# 05_FPGA_Interface.net
KiCad netlist of a schematic drawn in Altium Designer
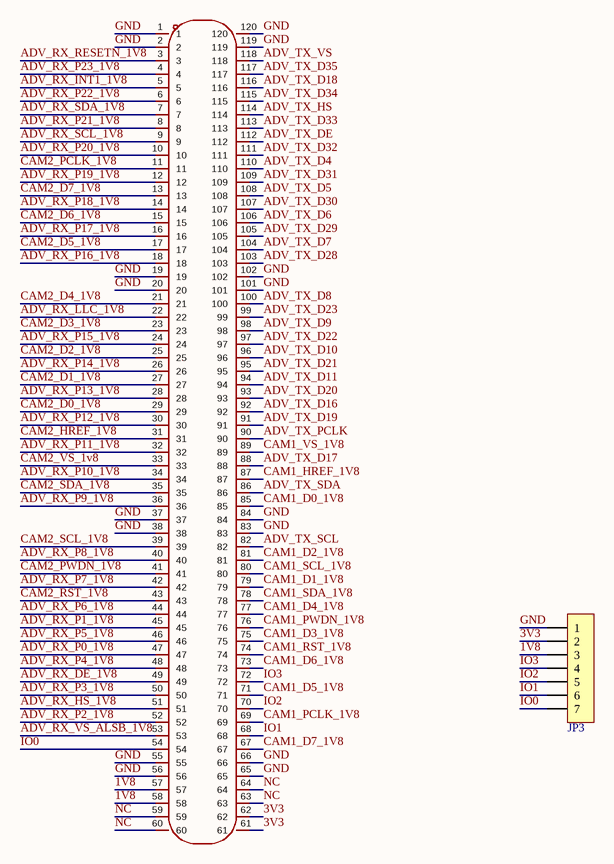
[diagram p0: 05_FPGA_Interface.SchDoc]

(export (version "E")
  (design (tool "Eeschema 10.0.6"))
  (components
    (comp (ref "CN1")
      (value "xdb612-120p-cor")
      (footprint "CONN-SMD_120P-P0.80_THD0812F-120BV-GF")
      (description "PIN总数:120P;间距:0.8mm;安装方式:立贴;排数:2;额定电流:500mA;工作温度:-45℃~+80℃;")
      (fields (field (name "MANUFACTURER") "LX(连欣科技)") (field (name "MANUFACTURERPART") "XDB612-120P-COR"))
      (libsource (lib "0.0self_build") (part "xdb612-120p-cor"))
    )
    (comp (ref "JP3")
      (value "HDR-1X7")
      (footprint "HDR2.54-LI-7P")
      (description "7P接插件")
      (fields (field (name "版权归属") "封装库来自淘宝 ID：黄晶宝石"))
      (libsource (lib "5.3 - 接插件-脚距2.54 (100mil) ") (part "Header 7"))
    )
  )
  (nets
    (net (code "1") (name "/1V8") (class "Default")
      (node (ref "CN1") (pin "57") (pinfunction "57_57") (pintype "passive"))
      (node (ref "CN1") (pin "58") (pinfunction "58_58") (pintype "passive"))
      (node (ref "JP3") (pin "3") (pinfunction "3_3") (pintype "passive"))
    )
    (net (code "2") (name "/3V3") (class "Default")
      (node (ref "CN1") (pin "61") (pinfunction "61_61") (pintype "passive"))
      (node (ref "CN1") (pin "62") (pinfunction "62_62") (pintype "passive"))
      (node (ref "JP3") (pin "2") (pinfunction "2_2") (pintype "passive"))
    )
    (net (code "3") (name "/ADV_RX_DE_1V8") (class "Default")
      (node (ref "CN1") (pin "49") (pinfunction "49_49") (pintype "passive"))
    )
    (net (code "4") (name "/ADV_RX_HS_1V8") (class "Default")
      (node (ref "CN1") (pin "51") (pinfunction "51_51") (pintype "passive"))
    )
    (net (code "5") (name "/ADV_RX_INT1_1V8") (class "Default")
      (node (ref "CN1") (pin "5") (pinfunction "5_5") (pintype "passive"))
    )
    (net (code "6") (name "/ADV_RX_LLC_1V8") (class "Default")
      (node (ref "CN1") (pin "22") (pinfunction "22_22") (pintype "passive"))
    )
    (net (code "7") (name "/ADV_RX_P0_1V8") (class "Default")
      (node (ref "CN1") (pin "47") (pinfunction "47_47") (pintype "passive"))
    )
    (net (code "8") (name "/ADV_RX_P1_1V8") (class "Default")
      (node (ref "CN1") (pin "45") (pinfunction "45_45") (pintype "passive"))
    )
    (net (code "9") (name "/ADV_RX_P2_1V8") (class "Default")
      (node (ref "CN1") (pin "52") (pinfunction "52_52") (pintype "passive"))
    )
    (net (code "10") (name "/ADV_RX_P3_1V8") (class "Default")
      (node (ref "CN1") (pin "50") (pinfunction "50_50") (pintype "passive"))
    )
    (net (code "11") (name "/ADV_RX_P4_1V8") (class "Default")
      (node (ref "CN1") (pin "48") (pinfunction "48_48") (pintype "passive"))
    )
    (net (code "12") (name "/ADV_RX_P5_1V8") (class "Default")
      (node (ref "CN1") (pin "46") (pinfunction "46_46") (pintype "passive"))
    )
    (net (code "13") (name "/ADV_RX_P6_1V8") (class "Default")
      (node (ref "CN1") (pin "44") (pinfunction "44_44") (pintype "passive"))
    )
    (net (code "14") (name "/ADV_RX_P7_1V8") (class "Default")
      (node (ref "CN1") (pin "42") (pinfunction "42_42") (pintype "passive"))
    )
    (net (code "15") (name "/ADV_RX_P8_1V8") (class "Default")
      (node (ref "CN1") (pin "40") (pinfunction "40_40") (pintype "passive"))
    )
    (net (code "16") (name "/ADV_RX_P9_1V8") (class "Default")
      (node (ref "CN1") (pin "36") (pinfunction "36_36") (pintype "passive"))
    )
    (net (code "17") (name "/ADV_RX_P10_1V8") (class "Default")
      (node (ref "CN1") (pin "34") (pinfunction "34_34") (pintype "passive"))
    )
    (net (code "18") (name "/ADV_RX_P11_1V8") (class "Default")
      (node (ref "CN1") (pin "32") (pinfunction "32_32") (pintype "passive"))
    )
    (net (code "19") (name "/ADV_RX_P12_1V8") (class "Default")
      (node (ref "CN1") (pin "30") (pinfunction "30_30") (pintype "passive"))
    )
    (net (code "20") (name "/ADV_RX_P13_1V8") (class "Default")
      (node (ref "CN1") (pin "28") (pinfunction "28_28") (pintype "passive"))
    )
    (net (code "21") (name "/ADV_RX_P14_1V8") (class "Default")
      (node (ref "CN1") (pin "26") (pinfunction "26_26") (pintype "passive"))
    )
    (net (code "22") (name "/ADV_RX_P15_1V8") (class "Default")
      (node (ref "CN1") (pin "24") (pinfunction "24_24") (pintype "passive"))
    )
    (net (code "23") (name "/ADV_RX_P16_1V8") (class "Default")
      (node (ref "CN1") (pin "18") (pinfunction "18_18") (pintype "passive"))
    )
    (net (code "24") (name "/ADV_RX_P17_1V8") (class "Default")
      (node (ref "CN1") (pin "16") (pinfunction "16_16") (pintype "passive"))
    )
    (net (code "25") (name "/ADV_RX_P18_1V8") (class "Default")
      (node (ref "CN1") (pin "14") (pinfunction "14_14") (pintype "passive"))
    )
    (net (code "26") (name "/ADV_RX_P19_1V8") (class "Default")
      (node (ref "CN1") (pin "12") (pinfunction "12_12") (pintype "passive"))
    )
    (net (code "27") (name "/ADV_RX_P20_1V8") (class "Default")
      (node (ref "CN1") (pin "10") (pinfunction "10_10") (pintype "passive"))
    )
    (net (code "28") (name "/ADV_RX_P21_1V8") (class "Default")
      (node (ref "CN1") (pin "8") (pinfunction "8_8") (pintype "passive"))
    )
    (net (code "29") (name "/ADV_RX_P22_1V8") (class "Default")
      (node (ref "CN1") (pin "6") (pinfunction "6_6") (pintype "passive"))
    )
    (net (code "30") (name "/ADV_RX_P23_1V8") (class "Default")
      (node (ref "CN1") (pin "4") (pinfunction "4_4") (pintype "passive"))
    )
    (net (code "31") (name "/ADV_RX_RESETN_1V8") (class "Default")
      (node (ref "CN1") (pin "3") (pinfunction "3_3") (pintype "passive"))
    )
    (net (code "32") (name "/ADV_RX_SCL_1V8") (class "Default")
      (node (ref "CN1") (pin "9") (pinfunction "9_9") (pintype "passive"))
    )
    (net (code "33") (name "/ADV_RX_SDA_1V8") (class "Default")
      (node (ref "CN1") (pin "7") (pinfunction "7_7") (pintype "passive"))
    )
    (net (code "34") (name "/ADV_RX_VS_ALSB_1V8") (class "Default")
      (node (ref "CN1") (pin "53") (pinfunction "53_53") (pintype "passive"))
    )
    (net (code "35") (name "/ADV_TX_D4") (class "Default")
      (node (ref "CN1") (pin "110") (pinfunction "110_110") (pintype "passive"))
    )
    (net (code "36") (name "/ADV_TX_D5") (class "Default")
      (node (ref "CN1") (pin "108") (pinfunction "108_108") (pintype "passive"))
    )
    (net (code "37") (name "/ADV_TX_D6") (class "Default")
      (node (ref "CN1") (pin "106") (pinfunction "106_106") (pintype "passive"))
    )
    (net (code "38") (name "/ADV_TX_D7") (class "Default")
      (node (ref "CN1") (pin "104") (pinfunction "104_104") (pintype "passive"))
    )
    (net (code "39") (name "/ADV_TX_D8") (class "Default")
      (node (ref "CN1") (pin "100") (pinfunction "100_100") (pintype "passive"))
    )
    (net (code "40") (name "/ADV_TX_D9") (class "Default")
      (node (ref "CN1") (pin "98") (pinfunction "98_98") (pintype "passive"))
    )
    (net (code "41") (name "/ADV_TX_D10") (class "Default")
      (node (ref "CN1") (pin "96") (pinfunction "96_96") (pintype "passive"))
    )
    (net (code "42") (name "/ADV_TX_D11") (class "Default")
      (node (ref "CN1") (pin "94") (pinfunction "94_94") (pintype "passive"))
    )
    (net (code "43") (name "/ADV_TX_D16") (class "Default")
      (node (ref "CN1") (pin "92") (pinfunction "92_92") (pintype "passive"))
    )
    (net (code "44") (name "/ADV_TX_D17") (class "Default")
      (node (ref "CN1") (pin "88") (pinfunction "88_88") (pintype "passive"))
    )
    (net (code "45") (name "/ADV_TX_D18") (class "Default")
      (node (ref "CN1") (pin "116") (pinfunction "116_116") (pintype "passive"))
    )
    (net (code "46") (name "/ADV_TX_D19") (class "Default")
      (node (ref "CN1") (pin "91") (pinfunction "91_91") (pintype "passive"))
    )
    (net (code "47") (name "/ADV_TX_D20") (class "Default")
      (node (ref "CN1") (pin "93") (pinfunction "93_93") (pintype "passive"))
    )
    (net (code "48") (name "/ADV_TX_D21") (class "Default")
      (node (ref "CN1") (pin "95") (pinfunction "95_95") (pintype "passive"))
    )
    (net (code "49") (name "/ADV_TX_D22") (class "Default")
      (node (ref "CN1") (pin "97") (pinfunction "97_97") (pintype "passive"))
    )
    (net (code "50") (name "/ADV_TX_D23") (class "Default")
      (node (ref "CN1") (pin "99") (pinfunction "99_99") (pintype "passive"))
    )
    (net (code "51") (name "/ADV_TX_D28") (class "Default")
      (node (ref "CN1") (pin "103") (pinfunction "103_103") (pintype "passive"))
    )
    (net (code "52") (name "/ADV_TX_D29") (class "Default")
      (node (ref "CN1") (pin "105") (pinfunction "105_105") (pintype "passive"))
    )
    (net (code "53") (name "/ADV_TX_D30") (class "Default")
      (node (ref "CN1") (pin "107") (pinfunction "107_107") (pintype "passive"))
    )
    (net (code "54") (name "/ADV_TX_D31") (class "Default")
      (node (ref "CN1") (pin "109") (pinfunction "109_109") (pintype "passive"))
    )
    (net (code "55") (name "/ADV_TX_D32") (class "Default")
      (node (ref "CN1") (pin "111") (pinfunction "111_111") (pintype "passive"))
    )
    (net (code "56") (name "/ADV_TX_D33") (class "Default")
      (node (ref "CN1") (pin "113") (pinfunction "113_113") (pintype "passive"))
    )
    (net (code "57") (name "/ADV_TX_D34") (class "Default")
      (node (ref "CN1") (pin "115") (pinfunction "115_115") (pintype "passive"))
    )
    (net (code "58") (name "/ADV_TX_D35") (class "Default")
      (node (ref "CN1") (pin "117") (pinfunction "117_117") (pintype "passive"))
    )
    (net (code "59") (name "/ADV_TX_DE") (class "Default")
      (node (ref "CN1") (pin "112") (pinfunction "112_112") (pintype "passive"))
    )
    (net (code "60") (name "/ADV_TX_HS") (class "Default")
      (node (ref "CN1") (pin "114") (pinfunction "114_114") (pintype "passive"))
    )
    (net (code "61") (name "/ADV_TX_PCLK") (class "Default")
      (node (ref "CN1") (pin "90") (pinfunction "90_90") (pintype "passive"))
    )
    (net (code "62") (name "/ADV_TX_SCL") (class "Default")
      (node (ref "CN1") (pin "82") (pinfunction "82_82") (pintype "passive"))
    )
    (net (code "63") (name "/ADV_TX_SDA") (class "Default")
      (node (ref "CN1") (pin "86") (pinfunction "86_86") (pintype "passive"))
    )
    (net (code "64") (name "/ADV_TX_VS") (class "Default")
      (node (ref "CN1") (pin "118") (pinfunction "118_118") (pintype "passive"))
    )
    (net (code "65") (name "/CAM1_D0_1V8") (class "Default")
      (node (ref "CN1") (pin "85") (pinfunction "85_85") (pintype "passive"))
    )
    (net (code "66") (name "/CAM1_D1_1V8") (class "Default")
      (node (ref "CN1") (pin "79") (pinfunction "79_79") (pintype "passive"))
    )
    (net (code "67") (name "/CAM1_D2_1V8") (class "Default")
      (node (ref "CN1") (pin "81") (pinfunction "81_81") (pintype "passive"))
    )
    (net (code "68") (name "/CAM1_D3_1V8") (class "Default")
      (node (ref "CN1") (pin "75") (pinfunction "75_75") (pintype "passive"))
    )
    (net (code "69") (name "/CAM1_D4_1V8") (class "Default")
      (node (ref "CN1") (pin "77") (pinfunction "77_77") (pintype "passive"))
    )
    (net (code "70") (name "/CAM1_D5_1V8") (class "Default")
      (node (ref "CN1") (pin "71") (pinfunction "71_71") (pintype "passive"))
    )
    (net (code "71") (name "/CAM1_D6_1V8") (class "Default")
      (node (ref "CN1") (pin "73") (pinfunction "73_73") (pintype "passive"))
    )
    (net (code "72") (name "/CAM1_D7_1V8") (class "Default")
      (node (ref "CN1") (pin "67") (pinfunction "67_67") (pintype "passive"))
    )
    (net (code "73") (name "/CAM1_HREF_1V8") (class "Default")
      (node (ref "CN1") (pin "87") (pinfunction "87_87") (pintype "passive"))
    )
    (net (code "74") (name "/CAM1_PCLK_1V8") (class "Default")
      (node (ref "CN1") (pin "69") (pinfunction "69_69") (pintype "passive"))
    )
    (net (code "75") (name "/CAM1_PWDN_1V8") (class "Default")
      (node (ref "CN1") (pin "76") (pinfunction "76_76") (pintype "passive"))
    )
    (net (code "76") (name "/CAM1_RST_1V8") (class "Default")
      (node (ref "CN1") (pin "74") (pinfunction "74_74") (pintype "passive"))
    )
    (net (code "77") (name "/CAM1_SCL_1V8") (class "Default")
      (node (ref "CN1") (pin "80") (pinfunction "80_80") (pintype "passive"))
    )
    (net (code "78") (name "/CAM1_SDA_1V8") (class "Default")
      (node (ref "CN1") (pin "78") (pinfunction "78_78") (pintype "passive"))
    )
    (net (code "79") (name "/CAM1_VS_1V8") (class "Default")
      (node (ref "CN1") (pin "89") (pinfunction "89_89") (pintype "passive"))
    )
    (net (code "80") (name "/CAM2_D0_1V8") (class "Default")
      (node (ref "CN1") (pin "29") (pinfunction "29_29") (pintype "passive"))
    )
    (net (code "81") (name "/CAM2_D1_1V8") (class "Default")
      (node (ref "CN1") (pin "27") (pinfunction "27_27") (pintype "passive"))
    )
    (net (code "82") (name "/CAM2_D2_1V8") (class "Default")
      (node (ref "CN1") (pin "25") (pinfunction "25_25") (pintype "passive"))
    )
    (net (code "83") (name "/CAM2_D3_1V8") (class "Default")
      (node (ref "CN1") (pin "23") (pinfunction "23_23") (pintype "passive"))
    )
    (net (code "84") (name "/CAM2_D4_1V8") (class "Default")
      (node (ref "CN1") (pin "21") (pinfunction "21_21") (pintype "passive"))
    )
    (net (code "85") (name "/CAM2_D5_1V8") (class "Default")
      (node (ref "CN1") (pin "17") (pinfunction "17_17") (pintype "passive"))
    )
    (net (code "86") (name "/CAM2_D6_1V8") (class "Default")
      (node (ref "CN1") (pin "15") (pinfunction "15_15") (pintype "passive"))
    )
    (net (code "87") (name "/CAM2_D7_1V8") (class "Default")
      (node (ref "CN1") (pin "13") (pinfunction "13_13") (pintype "passive"))
    )
    (net (code "88") (name "/CAM2_HREF_1V8") (class "Default")
      (node (ref "CN1") (pin "31") (pinfunction "31_31") (pintype "passive"))
    )
    (net (code "89") (name "/CAM2_PCLK_1V8") (class "Default")
      (node (ref "CN1") (pin "11") (pinfunction "11_11") (pintype "passive"))
    )
    (net (code "90") (name "/CAM2_PWDN_1V8") (class "Default")
      (node (ref "CN1") (pin "41") (pinfunction "41_41") (pintype "passive"))
    )
    (net (code "91") (name "/CAM2_RST_1V8") (class "Default")
      (node (ref "CN1") (pin "43") (pinfunction "43_43") (pintype "passive"))
    )
    (net (code "92") (name "/CAM2_SCL_1V8") (class "Default")
      (node (ref "CN1") (pin "39") (pinfunction "39_39") (pintype "passive"))
    )
    (net (code "93") (name "/CAM2_SDA_1V8") (class "Default")
      (node (ref "CN1") (pin "35") (pinfunction "35_35") (pintype "passive"))
    )
    (net (code "94") (name "/CAM2_VS_1v8") (class "Default")
      (node (ref "CN1") (pin "33") (pinfunction "33_33") (pintype "passive"))
    )
    (net (code "95") (name "/GND") (class "Default")
      (node (ref "CN1") (pin "1") (pinfunction "1_1") (pintype "passive"))
      (node (ref "CN1") (pin "101") (pinfunction "101_101") (pintype "passive"))
      (node (ref "CN1") (pin "102") (pinfunction "102_102") (pintype "passive"))
      (node (ref "CN1") (pin "119") (pinfunction "119_119") (pintype "passive"))
      (node (ref "CN1") (pin "120") (pinfunction "120_120") (pintype "passive"))
      (node (ref "CN1") (pin "19") (pinfunction "19_19") (pintype "passive"))
      (node (ref "CN1") (pin "2") (pinfunction "2_2") (pintype "passive"))
      (node (ref "CN1") (pin "20") (pinfunction "20_20") (pintype "passive"))
      (node (ref "CN1") (pin "37") (pinfunction "37_37") (pintype "passive"))
      (node (ref "CN1") (pin "38") (pinfunction "38_38") (pintype "passive"))
      (node (ref "CN1") (pin "55") (pinfunction "55_55") (pintype "passive"))
      (node (ref "CN1") (pin "56") (pinfunction "56_56") (pintype "passive"))
      (node (ref "CN1") (pin "65") (pinfunction "65_65") (pintype "passive"))
      (node (ref "CN1") (pin "66") (pinfunction "66_66") (pintype "passive"))
      (node (ref "CN1") (pin "83") (pinfunction "83_83") (pintype "passive"))
      (node (ref "CN1") (pin "84") (pinfunction "84_84") (pintype "passive"))
      (node (ref "JP3") (pin "1") (pinfunction "1_1") (pintype "passive"))
    )
    (net (code "96") (name "/IO0") (class "Default")
      (node (ref "CN1") (pin "54") (pinfunction "54_54") (pintype "passive"))
      (node (ref "JP3") (pin "7") (pinfunction "7_7") (pintype "passive"))
    )
    (net (code "97") (name "/IO1") (class "Default")
      (node (ref "CN1") (pin "68") (pinfunction "68_68") (pintype "passive"))
      (node (ref "JP3") (pin "6") (pinfunction "6_6") (pintype "passive"))
    )
    (net (code "98") (name "/IO2") (class "Default")
      (node (ref "CN1") (pin "70") (pinfunction "70_70") (pintype "passive"))
      (node (ref "JP3") (pin "5") (pinfunction "5_5") (pintype "passive"))
    )
    (net (code "99") (name "/IO3") (class "Default")
      (node (ref "CN1") (pin "72") (pinfunction "72_72") (pintype "passive"))
      (node (ref "JP3") (pin "4") (pinfunction "4_4") (pintype "passive"))
    )
    (net (code "100") (name "/NC") (class "Default")
      (node (ref "CN1") (pin "59") (pinfunction "59_59") (pintype "passive"))
      (node (ref "CN1") (pin "60") (pinfunction "60_60") (pintype "passive"))
      (node (ref "CN1") (pin "63") (pinfunction "63_63") (pintype "passive"))
      (node (ref "CN1") (pin "64") (pinfunction "64_64") (pintype "passive"))
    )
  )
)
